# Main.net
KiCad netlist of a schematic drawn in Altium Designer
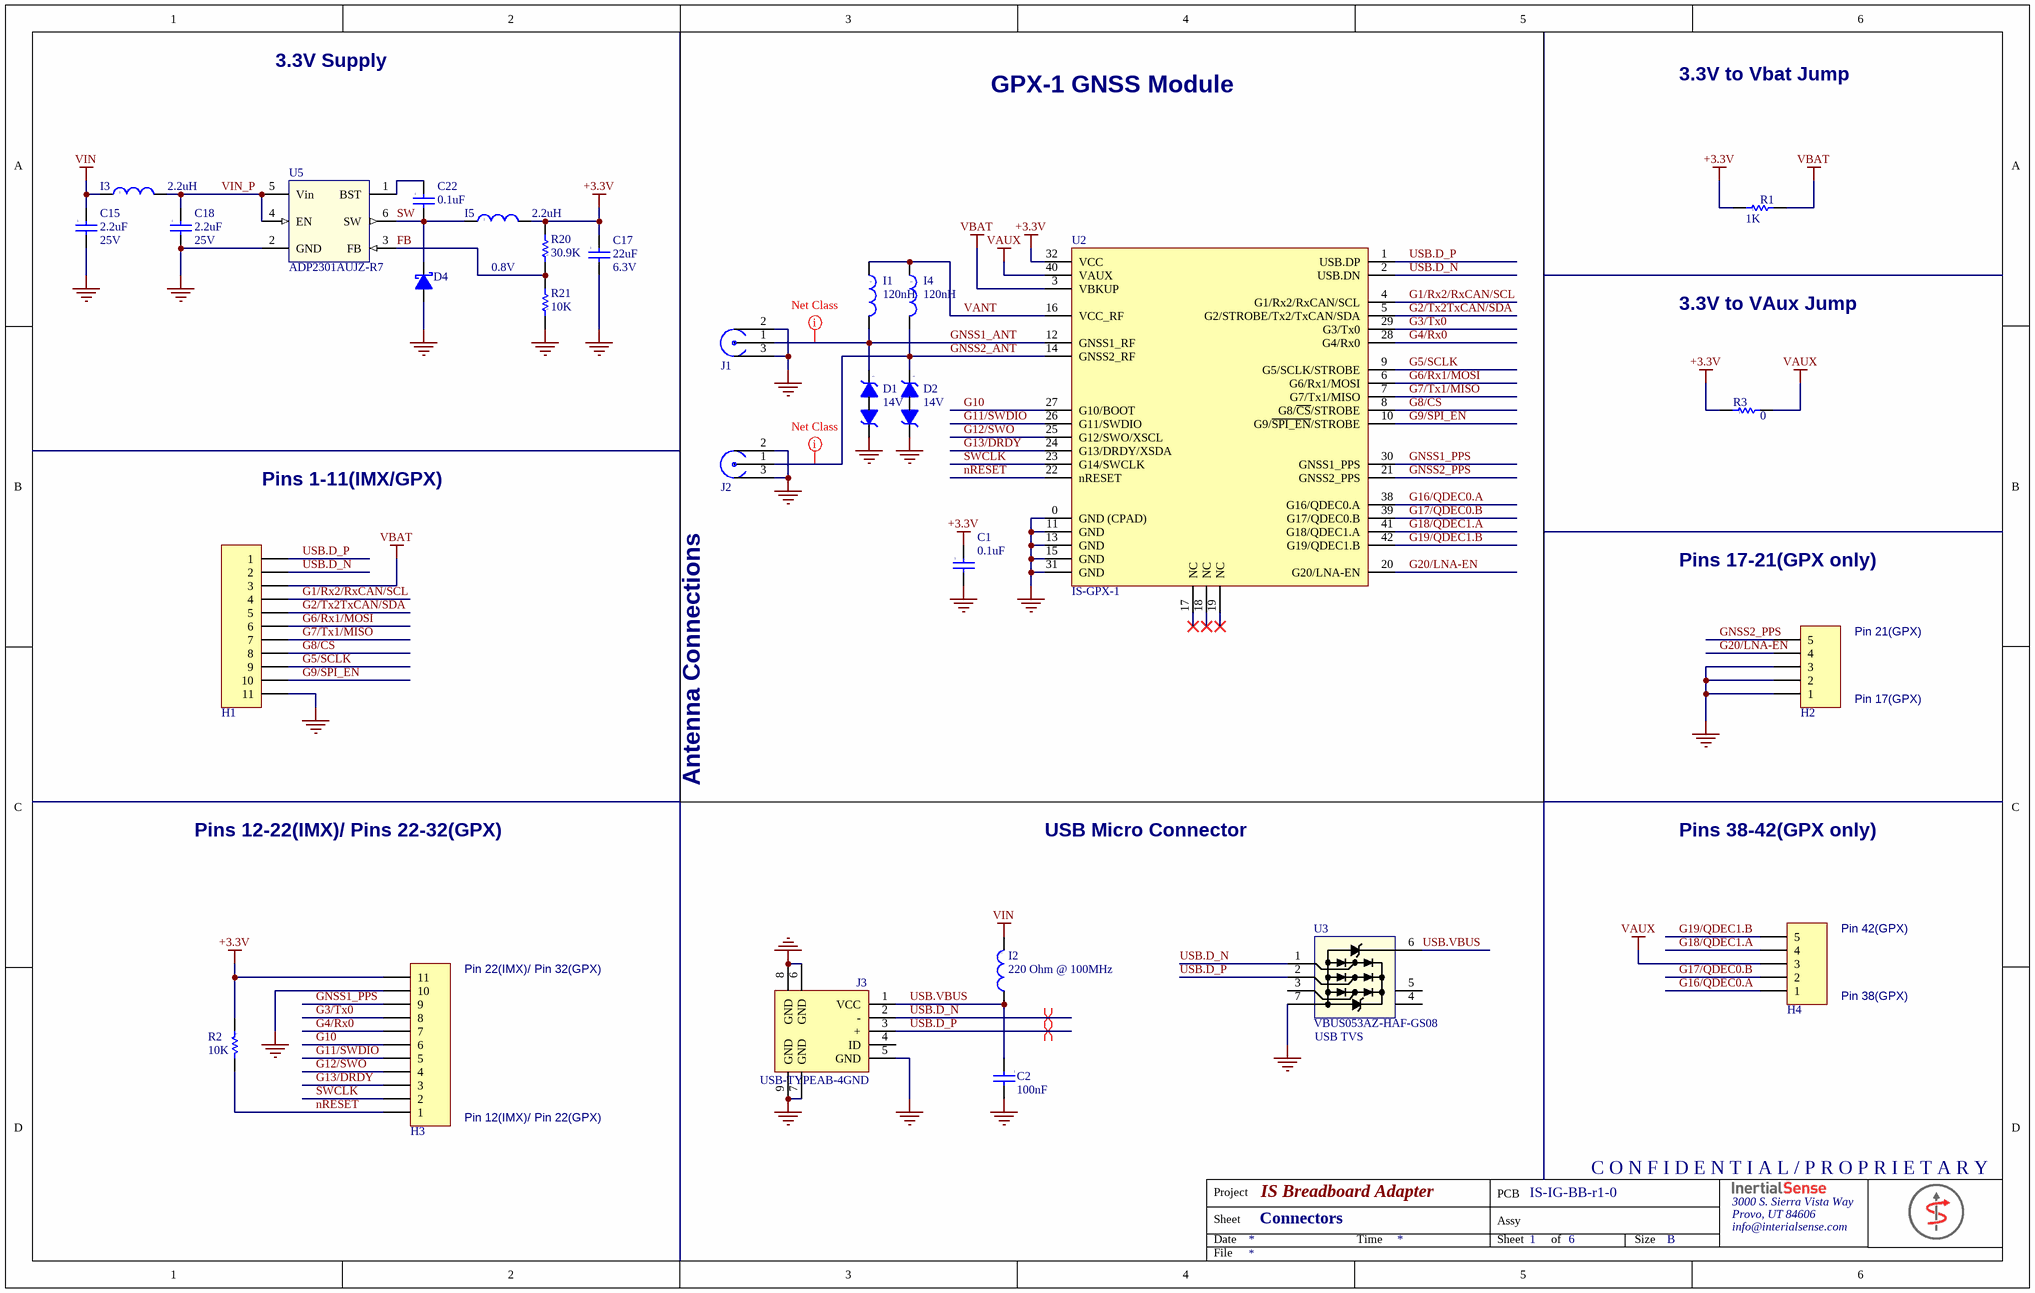
[diagram p0: Main.SchDoc]

(export (version "E")
  (design (tool "Eeschema 10.0.6"))
  (components
    (comp (ref "C1")
      (value "0.1uF")
      (footprint "0402")
      (description "CAP CER .10UF 50V X7R 10% 0402")
      (fields
        (field (name "MANUFACTURER") "TDK Corporation")
        (field (name "MANUFACTURER PART NUMBER") "C1005X7R1H104K")
        (field (name "PUBLISHER") "Altium Limited")
      )
      (libsource (lib "General") (part "Cap"))
    )
    (comp (ref "C2")
      (value "100nF")
      (footprint "0402")
      (description "CAP CER .10UF 50V X7R 10% 0402")
      (fields
        (field (name "MANUFACTURER") "TDK Corporation")
        (field (name "MANUFACTURER PART NUMBER") "C1005X7R1H104K")
        (field (name "PUBLISHER") "Altium Limited")
      )
      (libsource (lib "General") (part "Cap"))
    )
    (comp (ref "C15")
      (value "2.2uF")
      (footprint "0603")
      (description "CAP CER 2.2UF 25V X6S 0603")
      (fields
        (field (name "MANUFACTURER") "Murata")
        (field (name "MANUFACTURER PART NUMBER") "GRT188C81E225KE13D")
        (field (name "VOLTAGE RATING") "25V")
        (field (name "PUBLISHER") "Altium Limited")
      )
      (libsource (lib "General") (part "Cap"))
    )
    (comp (ref "C17")
      (value "22uF")
      (footprint "0603")
      (description "CAP CER 22UF 6.3V X6S 0603")
      (fields
        (field (name "MANUFACTURER") "Murata")
        (field (name "MANUFACTURER PART NUMBER") "GRM188C80J226ME15D")
        (field (name "VOLTAGE RATING") "6.3V")
        (field (name "PUBLISHER") "Altium Limited")
      )
      (libsource (lib "General") (part "Cap"))
    )
    (comp (ref "C18")
      (value "2.2uF")
      (footprint "0603")
      (description "CAP CER 2.2UF 25V X6S 0603")
      (fields
        (field (name "MANUFACTURER") "Murata")
        (field (name "MANUFACTURER PART NUMBER") "GRT188C81E225KE13D")
        (field (name "VOLTAGE RATING") "25V")
        (field (name "PUBLISHER") "Altium Limited")
      )
      (libsource (lib "General") (part "Cap"))
    )
    (comp (ref "C22")
      (value "0.1uF")
      (footprint "0402")
      (description "CAP CER 0.1UF 50V X7R 0402")
      (fields
        (field (name "MANUFACTURER") "TDK")
        (field (name "MANUFACTURER PART NUMBER") "CGA2B3X7R1H104K050BB")
        (field (name "PUBLISHER") "Altium Limited")
      )
      (libsource (lib "General") (part "Cap"))
    )
    (comp (ref "D1")
      (value "Diode - Bidirectional Zener")
      (footprint "R0402")
      (description "LITTELFUSE - PESD0402-140 - DIODE, ESD PROTECTION, 0402, FULL REEL")
      (fields
        (field (name "MANUFACTURER") "Littelfuse")
        (field (name "MANUFACTURER PART NUMBER") "PESD0402-140")
        (field (name "WORKING VOLTAGE") "14V")
      )
      (libsource (lib "General") (part "Diode - Bidirectional Zener"))
    )
    (comp (ref "D2")
      (value "Diode - Bidirectional Zener")
      (footprint "R0402")
      (description "LITTELFUSE - PESD0402-140 - DIODE, ESD PROTECTION, 0402, FULL REEL")
      (fields
        (field (name "MANUFACTURER") "Littelfuse")
        (field (name "MANUFACTURER PART NUMBER") "PESD0402-140")
        (field (name "WORKING VOLTAGE") "14V")
      )
      (libsource (lib "General") (part "Diode - Bidirectional Zener"))
    )
    (comp (ref "D4")
      (value "Diode - Schottky")
      (footprint "D0603B")
      (description "DIODE SCHOTTKY 30V 2A 0603")
      (fields
        (field (name "MANUFACTURER") "Vishay")
        (field (name "MANUFACTURER PART NUMBER") "VSKY20301608-G4-08")
      )
      (libsource (lib "General") (part "Diode - Schottky"))
    )
    (comp (ref "H1")
      (value "Hdr - 11pin")
      (footprint "Header-.1IN-1x11")
      (description "11 pin header")
      (libsource (lib "IS-IG-BB") (part "Hdr - 11pin"))
    )
    (comp (ref "H2")
      (value "Hdr - 5pin")
      (footprint "Header-.1IN-1x5")
      (description "5 pin header")
      (libsource (lib "IS-IG-BB") (part "Hdr - 5pin"))
    )
    (comp (ref "H3")
      (value "Hdr - 11pin")
      (footprint "Header-.1IN-1x11")
      (description "11 pin header")
      (libsource (lib "") (part "Hdr - 11pin_1"))
    )
    (comp (ref "H4")
      (value "Hdr - 5pin")
      (footprint "Header-.1IN-1x5")
      (description "5 pin header")
      (libsource (lib "IS-IG-BB") (part "Hdr - 5pin"))
    )
    (comp (ref "I1")
      (value "120nH")
      (footprint "0402")
      (description "Inductor RF Chip Wirewound 120nH 5% 100MHz 20Q-Factor 110mA 2.66Ohm DCR 0402 Paper T/R")
      (fields
        (field (name "MANUFACTURER") "Murata")
        (field (name "MANUFACTURER PART NUMBER") "LQW15ANR12J00D")
      )
      (libsource (lib "General") (part "Inductor"))
    )
    (comp (ref "I2")
      (value "220 Ohm @ 100MHz")
      (footprint "I0603")
      (description "FERRITE CHIP 220 OHM 2500MA 0603")
      (fields
        (field (name "MANUFACTURER") "Murata Electronics North America")
        (field (name "MANUFACTURER PART NUMBER") "BLM18SG221TN1D")
      )
      (libsource (lib "") (part "Inductor_1"))
    )
    (comp (ref "I3")
      (value "2.2uH")
      (footprint "0806")
      (description "FIXED IND 2.2UH 1.2A 110 MOHM")
      (fields
        (field (name "MANUFACTURER") "TDK")
        (field (name "MANUFACTURER PART NUMBER") "MLP2016H2R2MT0S1")
      )
      (libsource (lib "General") (part "Inductor"))
    )
    (comp (ref "I4")
      (value "120nH")
      (footprint "0402")
      (description "Inductor RF Chip Wirewound 120nH 5% 100MHz 20Q-Factor 110mA 2.66Ohm DCR 0402 Paper T/R")
      (fields
        (field (name "MANUFACTURER") "Murata")
        (field (name "MANUFACTURER PART NUMBER") "LQW15ANR12J00D")
      )
      (libsource (lib "General") (part "Inductor"))
    )
    (comp (ref "I5")
      (value "2.2uH")
      (footprint "0806")
      (description "FIXED IND 2.2UH 1.2A 110 MOHM")
      (fields
        (field (name "MANUFACTURER") "TDK")
        (field (name "MANUFACTURER PART NUMBER") "MLP2016H2R2MT0S1")
      )
      (libsource (lib "General") (part "Inductor"))
    )
    (comp (ref "J1")
      (value "RF - GND x 2")
      (footprint "RF UMC SMD")
      (description "CONN UMC RCPT STR 50 OHM SMD")
      (fields
        (field (name "MANUFACTURER") "Emerson Network Power Connectivity Johnson")
        (field (name "MANUFACTURER PART NUMBER") "128-0711-201")
      )
      (libsource (lib "Connectors") (part "RF - GND x 2"))
    )
    (comp (ref "J2")
      (value "RF - GND x 2")
      (footprint "RF UMC SMD")
      (description "CONN UMC RCPT STR 50 OHM SMD")
      (fields
        (field (name "MANUFACTURER") "Emerson Network Power Connectivity Johnson")
        (field (name "MANUFACTURER PART NUMBER") "128-0711-201")
      )
      (libsource (lib "Connectors") (part "RF - GND x 2"))
    )
    (comp (ref "J3")
      (value "USB-TYPEAB-4GND")
      (footprint "USB Micro AB R/A THR")
      (description "CONN USB AB 4POS")
      (fields
        (field (name "MANUFACTURER") "Amphenol FCI")
        (field (name "MANUFACTURER PART NUMBER") "10118194-0001LF")
      )
      (libsource (lib "Connectors") (part "USB-TYPEAB-4GND"))
    )
    (comp (ref "R1")
      (value "1K")
      (footprint "R0402")
      (description "1 kOhms ±1% 0.063W, 1/16W Chip Resistor 0402 (1005 Metric) Moisture Resistant Thick Film")
      (fields
        (field (name "MANUFACTURER") "Yageo")
        (field (name "MANUFACTURER PART NUMBER") "RC0402FR-071KL")
      )
      (libsource (lib "General") (part "Res"))
    )
    (comp (ref "R2")
      (value "10K")
      (footprint "R0402")
      (description "1 kOhms ±1% 0.063W, 1/16W Chip Resistor 0402 (1005 Metric) Moisture Resistant Thick Film")
      (fields
        (field (name "MANUFACTURER") "Stackpole Electronics")
        (field (name "MANUFACTURER PART NUMBER") "RMCF0402FT10K0")
      )
      (libsource (lib "General") (part "Res"))
    )
    (comp (ref "R3")
      (value "0")
      (footprint "R0402")
      (description "1 kOhms ±1% 0.063W, 1/16W Chip Resistor 0402 (1005 Metric) Moisture Resistant Thick Film")
      (fields
        (field (name "MANUFACTURER") "Yageo")
        (field (name "MANUFACTURER PART NUMBER") "RC0402FR-071KL")
      )
      (libsource (lib "General") (part "Res"))
    )
    (comp (ref "R20")
      (value "30.9K")
      (footprint "R0402")
      (description "RES TF 30.9K OHM 1% 1/16W 0402")
      (fields
        (field (name "MANUFACTURER") "Stackpole Electronics Inc")
        (field (name "MANUFACTURER PART NUMBER") "RMCF0402FT30K9")
      )
      (libsource (lib "General") (part "Res"))
    )
    (comp (ref "R21")
      (value "10K")
      (footprint "R0402")
      (description "RES 10.0K OHM 1/16W 1% 0402 SMD")
      (fields
        (field (name "MANUFACTURER") "Yageo")
        (field (name "MANUFACTURER PART NUMBER") "RC0402FR-0710KL")
      )
      (libsource (lib "General") (part "Res"))
    )
    (comp (ref "U2")
      (value "GPX")
      (footprint "IS-GPX-1.0")
      (description "Inertial Sense GPX")
      (fields
        (field (name "MANUFACTURER") "Inertial Sense")
        (field (name "MANUFACTURER PART NUMBER") "IS-GPX-1")
      )
      (libsource (lib "IS-GPX-1") (part "IS-GPX-1.0"))
    )
    (comp (ref "U3")
      (value "VBUS053")
      (footprint "QFN50P160X160X60-6N")
      (description "ESD SUPPRESS 5.5V 36W 3-Line USB")
      (fields
        (field (name "MANUFACTURER") "Vishay Semiconductors")
        (field (name "MANUFACTURER PART NUMBER") "VBUS053AZ-HAF-GS08")
      )
      (libsource (lib "ICs") (part "VBUS053"))
    )
    (comp (ref "U5")
      (value "ADP2301")
      (footprint "MO-178-AB")
      (description "IC BUCK ADJ 1.2A 6TSOT")
      (fields
        (field (name "MANUFACTURER") "Analog Devices Inc")
        (field (name "MANUFACTURER PART NUMBER") "ADP2301AUJZ-R7")
      )
      (libsource (lib "ICs") (part "ADP2301"))
    )
  )
  (nets
    (net (code "1") (name "+3.3V") (class "Default")
      (node (ref "C1") (pin "1") (pinfunction "1_1") (pintype "passive"))
      (node (ref "C17") (pin "1") (pinfunction "1_1") (pintype "passive"))
      (node (ref "H3") (pin "11") (pinfunction "11_11") (pintype "passive"))
      (node (ref "I5") (pin "2") (pinfunction "2_2") (pintype "passive"))
      (node (ref "R1") (pin "1") (pinfunction "1_1") (pintype "passive"))
      (node (ref "R2") (pin "1") (pinfunction "1_1") (pintype "passive"))
      (node (ref "R20") (pin "2") (pinfunction "2_2") (pintype "passive"))
      (node (ref "R3") (pin "1") (pinfunction "1_1") (pintype "passive"))
      (node (ref "U2") (pin "32") (pinfunction "VCC_32") (pintype "power_in"))
    )
    (net (code "3") (name "/FB") (class "Default")
      (node (ref "R20") (pin "1") (pinfunction "1_1") (pintype "passive"))
      (node (ref "R21") (pin "2") (pinfunction "2_2") (pintype "passive"))
      (node (ref "U5") (pin "3") (pinfunction "FB_3") (pintype "input"))
    )
    (net (code "4") (name "/G1{slash}Rx2{slash}RxCAN{slash}SCL") (class "Default")
      (node (ref "H1") (pin "4") (pinfunction "4_4") (pintype "passive"))
      (node (ref "U2") (pin "4") (pinfunction "G1/Rx2/RxCAN/SCL_4") (pintype "passive"))
    )
    (net (code "5") (name "/G2{slash}Tx2TxCAN{slash}SDA") (class "Default")
      (node (ref "H1") (pin "5") (pinfunction "5_5") (pintype "passive"))
      (node (ref "U2") (pin "5") (pinfunction "G2/STROBE/Tx2/TxCAN/SDA_5") (pintype "passive"))
    )
    (net (code "6") (name "/G3{slash}Tx0") (class "Default")
      (node (ref "H3") (pin "8") (pinfunction "8_8") (pintype "passive"))
      (node (ref "U2") (pin "29") (pinfunction "G3/Tx0_29") (pintype "passive"))
    )
    (net (code "7") (name "/G4{slash}Rx0") (class "Default")
      (node (ref "H3") (pin "7") (pinfunction "7_7") (pintype "passive"))
      (node (ref "U2") (pin "28") (pinfunction "G4/Rx0_28") (pintype "passive"))
    )
    (net (code "8") (name "/G5{slash}SCLK") (class "Default")
      (node (ref "H1") (pin "9") (pinfunction "9_9") (pintype "passive"))
      (node (ref "U2") (pin "9") (pinfunction "G5/SCLK/STROBE_9") (pintype "passive"))
    )
    (net (code "9") (name "/G6{slash}Rx1{slash}MOSI") (class "Default")
      (node (ref "H1") (pin "6") (pinfunction "6_6") (pintype "passive"))
      (node (ref "U2") (pin "6") (pinfunction "G6/Rx1/MOSI_6") (pintype "passive"))
    )
    (net (code "10") (name "/G7{slash}Tx1{slash}MISO") (class "Default")
      (node (ref "H1") (pin "7") (pinfunction "7_7") (pintype "passive"))
      (node (ref "U2") (pin "7") (pinfunction "G7/Tx1/MISO_7") (pintype "passive"))
    )
    (net (code "11") (name "/G8{slash}~{CS}") (class "Default")
      (node (ref "H1") (pin "8") (pinfunction "8_8") (pintype "passive"))
      (node (ref "U2") (pin "8") (pinfunction "G8/~{CS}/STROBE_8") (pintype "passive"))
    )
    (net (code "12") (name "/G9{slash}~{SPI_EN}") (class "Default")
      (node (ref "H1") (pin "10") (pinfunction "10_10") (pintype "passive"))
      (node (ref "U2") (pin "10") (pinfunction "G9/~{SPI_EN}/STROBE_10") (pintype "passive"))
    )
    (net (code "13") (name "/G10") (class "Default")
      (node (ref "H3") (pin "6") (pinfunction "6_6") (pintype "passive"))
      (node (ref "U2") (pin "27") (pinfunction "G10/BOOT_27") (pintype "passive"))
    )
    (net (code "14") (name "/G11{slash}SWDIO") (class "Default")
      (node (ref "H3") (pin "5") (pinfunction "5_5") (pintype "passive"))
      (node (ref "U2") (pin "26") (pinfunction "G11/SWDIO_26") (pintype "passive"))
    )
    (net (code "15") (name "/G12{slash}SWO") (class "Default")
      (node (ref "H3") (pin "4") (pinfunction "4_4") (pintype "passive"))
      (node (ref "U2") (pin "25") (pinfunction "G12/SWO/XSCL_25") (pintype "passive"))
    )
    (net (code "16") (name "/G13{slash}DRDY") (class "Default")
      (node (ref "H3") (pin "3") (pinfunction "3_3") (pintype "passive"))
      (node (ref "U2") (pin "24") (pinfunction "G13/DRDY/XSDA_24") (pintype "passive"))
    )
    (net (code "17") (name "/G16{slash}QDEC0.A") (class "Default")
      (node (ref "H4") (pin "1") (pinfunction "1_1") (pintype "passive"))
      (node (ref "U2") (pin "38") (pinfunction "G16/QDEC0.A_38") (pintype "passive"))
    )
    (net (code "18") (name "/G17{slash}QDEC0.B") (class "Default")
      (node (ref "H4") (pin "2") (pinfunction "2_2") (pintype "passive"))
      (node (ref "U2") (pin "39") (pinfunction "G17/QDEC0.B_39") (pintype "passive"))
    )
    (net (code "19") (name "/G18{slash}QDEC1.A") (class "Default")
      (node (ref "H4") (pin "4") (pinfunction "4_4") (pintype "passive"))
      (node (ref "U2") (pin "41") (pinfunction "G18/QDEC1.A_41") (pintype "passive"))
    )
    (net (code "20") (name "/G19{slash}QDEC1.B") (class "Default")
      (node (ref "H4") (pin "5") (pinfunction "5_5") (pintype "passive"))
      (node (ref "U2") (pin "42") (pinfunction "G19/QDEC1.B_42") (pintype "passive"))
    )
    (net (code "21") (name "/G20{slash}LNA-EN") (class "Default")
      (node (ref "H2") (pin "4") (pinfunction "4_4") (pintype "passive"))
      (node (ref "U2") (pin "20") (pinfunction "G20/LNA-EN_20") (pintype "passive"))
    )
    (net (code "22") (name "/GNSS1_ANT") (class "Default")
      (node (ref "D1") (pin "1") (pinfunction "1_1") (pintype "passive"))
      (node (ref "I1") (pin "2") (pinfunction "2_2") (pintype "passive"))
      (node (ref "J1") (pin "1") (pinfunction "1_1") (pintype "passive"))
      (node (ref "U2") (pin "12") (pinfunction "GNSS1_RF_12") (pintype "passive"))
    )
    (net (code "23") (name "/GNSS1_PPS") (class "Default")
      (node (ref "H3") (pin "9") (pinfunction "9_9") (pintype "passive"))
      (node (ref "U2") (pin "30") (pinfunction "GNSS1_PPS_30") (pintype "passive"))
    )
    (net (code "24") (name "/GNSS2_ANT") (class "Default")
      (node (ref "D2") (pin "1") (pinfunction "1_1") (pintype "passive"))
      (node (ref "I4") (pin "2") (pinfunction "2_2") (pintype "passive"))
      (node (ref "J2") (pin "1") (pinfunction "1_1") (pintype "passive"))
      (node (ref "U2") (pin "14") (pinfunction "GNSS2_RF_14") (pintype "passive"))
    )
    (net (code "25") (name "/GNSS2_PPS") (class "Default")
      (node (ref "H2") (pin "5") (pinfunction "5_5") (pintype "passive"))
      (node (ref "U2") (pin "21") (pinfunction "GNSS2_PPS_21") (pintype "passive"))
    )
    (net (code "26") (name "/SW") (class "Default")
      (node (ref "C22") (pin "2") (pinfunction "2_2") (pintype "passive"))
      (node (ref "D4") (pin "C") (pinfunction "C_C") (pintype "passive"))
      (node (ref "I5") (pin "1") (pinfunction "1_1") (pintype "passive"))
      (node (ref "U5") (pin "6") (pinfunction "SW_6") (pintype "output"))
    )
    (net (code "27") (name "/SWCLK") (class "Default")
      (node (ref "H3") (pin "2") (pinfunction "2_2") (pintype "passive"))
      (node (ref "U2") (pin "23") (pinfunction "G14/SWCLK_23") (pintype "passive"))
    )
    (net (code "28") (name "/USB.D_N") (class "Default")
      (node (ref "H1") (pin "2") (pinfunction "2_2") (pintype "passive"))
      (node (ref "J3") (pin "2") (pinfunction "-_2") (pintype "passive"))
      (node (ref "U2") (pin "2") (pinfunction "USB.DN_2") (pintype "passive"))
      (node (ref "U3") (pin "1") (pintype "passive"))
    )
    (net (code "29") (name "/USB.D_P") (class "Default")
      (node (ref "H1") (pin "1") (pinfunction "1_1") (pintype "passive"))
      (node (ref "J3") (pin "3") (pinfunction "+_3") (pintype "passive"))
      (node (ref "U2") (pin "1") (pinfunction "USB.DP_1") (pintype "passive"))
      (node (ref "U3") (pin "2") (pintype "passive"))
    )
    (net (code "30") (name "/USB.VBUS") (class "Default")
      (node (ref "C2") (pin "1") (pinfunction "1_1") (pintype "passive"))
      (node (ref "I2") (pin "2") (pinfunction "2_2") (pintype "passive"))
      (node (ref "J3") (pin "1") (pinfunction "VCC_1") (pintype "passive"))
      (node (ref "U3") (pin "6") (pintype "passive"))
    )
    (net (code "31") (name "/VANT") (class "Default")
      (node (ref "I1") (pin "1") (pinfunction "1_1") (pintype "passive"))
      (node (ref "I4") (pin "1") (pinfunction "1_1") (pintype "passive"))
      (node (ref "U2") (pin "16") (pinfunction "VCC_RF_16") (pintype "power_in"))
    )
    (net (code "32") (name "/VIN_P") (class "Default")
      (node (ref "C18") (pin "1") (pinfunction "1_1") (pintype "passive"))
      (node (ref "I3") (pin "2") (pinfunction "2_2") (pintype "passive"))
      (node (ref "U5") (pin "4") (pinfunction "EN_4") (pintype "input"))
      (node (ref "U5") (pin "5") (pinfunction "Vin_5") (pintype "power_in"))
    )
    (net (code "33") (name "/nRESET") (class "Default")
      (node (ref "H3") (pin "1") (pinfunction "1_1") (pintype "passive"))
      (node (ref "R2") (pin "2") (pinfunction "2_2") (pintype "passive"))
      (node (ref "U2") (pin "22") (pinfunction "nRESET_22") (pintype "passive"))
    )
    (net (code "34") (name "GND") (class "Default")
      (node (ref "C1") (pin "2") (pinfunction "2_2") (pintype "passive"))
      (node (ref "C15") (pin "2") (pinfunction "2_2") (pintype "passive"))
      (node (ref "C17") (pin "2") (pinfunction "2_2") (pintype "passive"))
      (node (ref "C18") (pin "2") (pinfunction "2_2") (pintype "passive"))
      (node (ref "C2") (pin "2") (pinfunction "2_2") (pintype "passive"))
      (node (ref "D1") (pin "2") (pinfunction "2_2") (pintype "passive"))
      (node (ref "D2") (pin "2") (pinfunction "2_2") (pintype "passive"))
      (node (ref "D4") (pin "A") (pinfunction "A_A") (pintype "passive"))
      (node (ref "H1") (pin "11") (pinfunction "11_11") (pintype "passive"))
      (node (ref "H2") (pin "1") (pinfunction "1_1") (pintype "passive"))
      (node (ref "H2") (pin "2") (pinfunction "2_2") (pintype "passive"))
      (node (ref "H2") (pin "3") (pinfunction "3_3") (pintype "passive"))
      (node (ref "H3") (pin "10") (pinfunction "10_10") (pintype "passive"))
      (node (ref "J1") (pin "2") (pinfunction "2_2") (pintype "passive"))
      (node (ref "J1") (pin "3") (pinfunction "3_3") (pintype "passive"))
      (node (ref "J2") (pin "2") (pinfunction "2_2") (pintype "passive"))
      (node (ref "J2") (pin "3") (pinfunction "3_3") (pintype "passive"))
      (node (ref "J3") (pin "5") (pinfunction "GND_5") (pintype "passive"))
      (node (ref "J3") (pin "6") (pinfunction "GND_6") (pintype "passive"))
      (node (ref "J3") (pin "7") (pinfunction "GND_7") (pintype "passive"))
      (node (ref "J3") (pin "8") (pinfunction "GND_8") (pintype "passive"))
      (node (ref "J3") (pin "9") (pinfunction "GND_9") (pintype "passive"))
      (node (ref "R21") (pin "1") (pinfunction "1_1") (pintype "passive"))
      (node (ref "U2") (pin "0") (pinfunction "GND_(CPAD)_0") (pintype "power_in"))
      (node (ref "U2") (pin "11") (pinfunction "GND_11") (pintype "power_in"))
      (node (ref "U2") (pin "13") (pinfunction "GND_13") (pintype "power_in"))
      (node (ref "U2") (pin "15") (pinfunction "GND_15") (pintype "power_in"))
      (node (ref "U2") (pin "31") (pinfunction "GND_31") (pintype "power_in"))
      (node (ref "U3") (pin "7") (pintype "passive"))
      (node (ref "U5") (pin "2") (pinfunction "GND_2") (pintype "power_in"))
    )
    (net (code "35") (name "Net-(U5-BST)") (class "Default")
      (node (ref "C22") (pin "1") (pinfunction "1_1") (pintype "passive"))
      (node (ref "U5") (pin "1") (pinfunction "BST_1") (pintype "passive"))
    )
    (net (code "36") (name "VAUX") (class "Default")
      (node (ref "H4") (pin "3") (pinfunction "3_3") (pintype "passive"))
      (node (ref "R3") (pin "2") (pinfunction "2_2") (pintype "passive"))
      (node (ref "U2") (pin "40") (pinfunction "VAUX_40") (pintype "power_in"))
    )
    (net (code "37") (name "VBAT") (class "Default")
      (node (ref "H1") (pin "3") (pinfunction "3_3") (pintype "passive"))
      (node (ref "R1") (pin "2") (pinfunction "2_2") (pintype "passive"))
      (node (ref "U2") (pin "3") (pinfunction "VBKUP_3") (pintype "passive"))
    )
    (net (code "38") (name "VIN") (class "Default")
      (node (ref "C15") (pin "1") (pinfunction "1_1") (pintype "passive"))
      (node (ref "I2") (pin "1") (pinfunction "1_1") (pintype "passive"))
      (node (ref "I3") (pin "1") (pinfunction "1_1") (pintype "passive"))
    )
    (net (code "39") (name "unconnected-(J3-ID-Pad4)") (class "Default")
      (node (ref "J3") (pin "4") (pinfunction "ID_4") (pintype "passive"))
    )
    (net (code "40") (name "unconnected-(U2-NC-Pad17)") (class "Default")
      (node (ref "U2") (pin "17") (pinfunction "NC_17") (pintype "passive+no_connect"))
    )
    (net (code "41") (name "unconnected-(U2-NC-Pad18)") (class "Default")
      (node (ref "U2") (pin "18") (pinfunction "NC_18") (pintype "passive+no_connect"))
    )
    (net (code "42") (name "unconnected-(U2-NC-Pad19)") (class "Default")
      (node (ref "U2") (pin "19") (pinfunction "NC_19") (pintype "passive+no_connect"))
    )
    (net (code "43") (name "unconnected-(U3-Pad3)") (class "Default")
      (node (ref "U3") (pin "3") (pintype "passive"))
    )
    (net (code "44") (name "unconnected-(U3-nc-Pad4)") (class "Default")
      (node (ref "U3") (pin "4") (pinfunction "nc_4") (pintype "passive"))
    )
    (net (code "45") (name "unconnected-(U3-nc-Pad5)") (class "Default")
      (node (ref "U3") (pin "5") (pinfunction "nc_5") (pintype "passive"))
    )
  )
)
